# RHN-JD-SCH11V1_00.net
KiCad netlist of a schematic drawn in Altium Designer
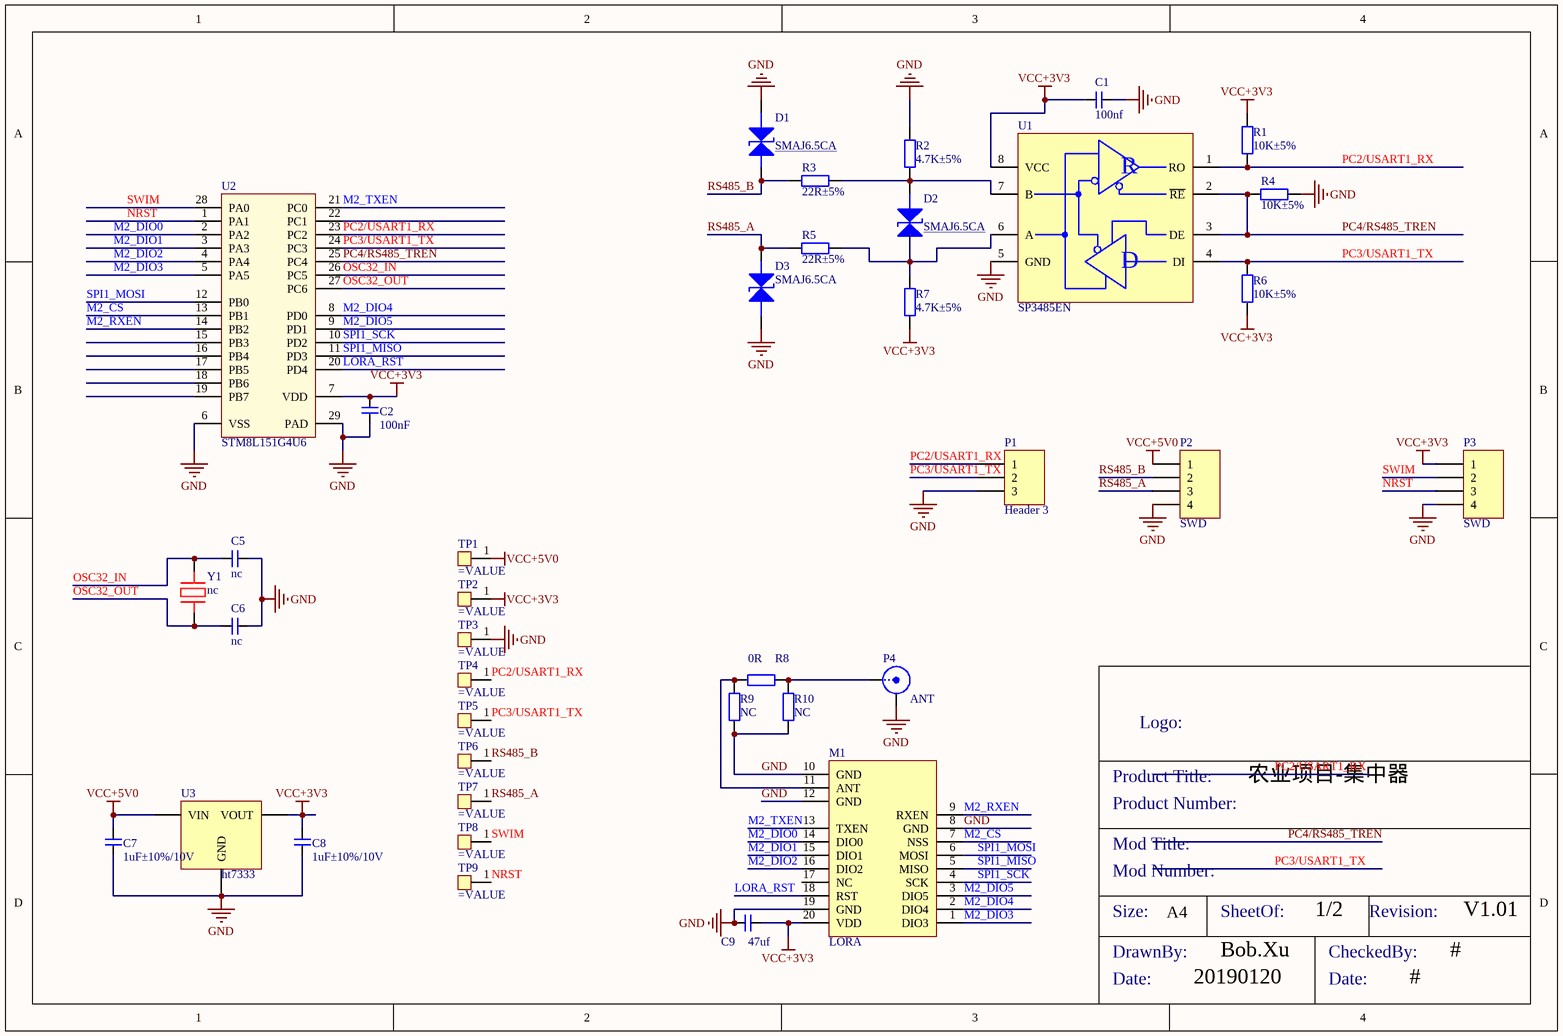
[diagram p0: RHN-JD-SCH11V1.00.SchDoc]

(export (version "E")
  (design (tool "Eeschema 10.0.6"))
  (components
    (comp (ref "C1")
      (value "100nf")
      (footprint "c0402")
      (description "无极性电容")
      (libsource (lib "瑞臻信息") (part "无极性电容"))
    )
    (comp (ref "C2")
      (value "100nF")
      (footprint "C0402")
      (description "无极性电容")
      (libsource (lib "瑞臻信息") (part "无极性电容"))
    )
    (comp (ref "C5")
      (value "nc")
      (footprint "C0402")
      (description "无极性电容")
      (libsource (lib "瑞臻信息") (part "无极性电容"))
    )
    (comp (ref "C6")
      (value "nc")
      (footprint "C0402")
      (description "无极性电容")
      (libsource (lib "瑞臻信息") (part "无极性电容"))
    )
    (comp (ref "C7")
      (value "1uF±10%/10V")
      (footprint "C0402")
      (description "MLCC_1uF±10%_10V_X5R_0402")
      (fields
        (field (name "PART NUMBER") "1.2.04.05.0024")
        (field (name "COMPONENTLINK1URL") "z:\\规格书\\02原材料\\04电容\\05瓷片电容\\三星电容.pdf")
        (field (name "PUBLISHER") "徐永伟")
        (field (name "EDIT NOTE") "V1.0-创建-20190329-徐永伟")
      )
      (libsource (lib "瑞臻信息") (part "无极性电容"))
    )
    (comp (ref "C8")
      (value "1uF±10%/10V")
      (footprint "C0402")
      (description "MLCC_1uF±10%_10V_X5R_0402")
      (fields
        (field (name "PART NUMBER") "1.2.04.05.0024")
        (field (name "COMPONENTLINK1URL") "z:\\规格书\\02原材料\\04电容\\05瓷片电容\\三星电容.pdf")
        (field (name "PUBLISHER") "徐永伟")
        (field (name "EDIT NOTE") "V1.0-创建-20190329-徐永伟")
      )
      (libsource (lib "瑞臻信息") (part "无极性电容"))
    )
    (comp (ref "C9")
      (value "47uf")
      (footprint "瑞臻信息:C1206")
      (description "无极性电容")
      (libsource (lib "瑞臻信息") (part "无极性电容"))
    )
    (comp (ref "D1")
      (value "SMAJ6.5CA")
      (footprint "SMB_2P_3R9X4R6")
      (description "半导体放电管-P821P0080SCLRP-200A(10/160us)-It2.2A/4Vt-6Vdrm-50pF-SMB")
      (libsource (lib "TM03-B_V01") (part "1.2.08.99.0052"))
    )
    (comp (ref "D2")
      (value "SMAJ6.5CA")
      (footprint "SMB_2P_3R9X4R6")
      (description "半导体放电管-P821P0080SCLRP-200A(10/160us)-It2.2A/4Vt-6Vdrm-50pF-SMB")
      (libsource (lib "TM03-B_V01") (part "1.2.08.99.0052"))
    )
    (comp (ref "D3")
      (value "SMAJ6.5CA")
      (footprint "SMB_2P_3R9X4R6")
      (description "半导体放电管-P821P0080SCLRP-200A(10/160us)-It2.2A/4Vt-6Vdrm-50pF-SMB")
      (libsource (lib "TM03-B_V01") (part "1.2.08.99.0052"))
    )
    (comp (ref "M1") (value "LORA") (footprint "LORA_PIN_1") (libsource (lib "瑞臻信息") (part "LORA_PIN_1")))
    (comp (ref "P1")
      (value "Header 3")
      (footprint "HDR1X3")
      (description "Header, 3-Pin")
      (fields (field (name "PUBLISHER") "Altium Limited"))
      (libsource (lib "Miscellaneous Connectors") (part "Header 3"))
    )
    (comp (ref "P2")
      (value "SWD")
      (footprint "HDR1X4")
      (description "Header, 4-Pin")
      (fields (field (name "PUBLISHER") "Altium Limited"))
      (libsource (lib "Miscellaneous Connectors") (part "Header 4"))
    )
    (comp (ref "P3")
      (value "SWD")
      (footprint "HDR1X4")
      (description "Header, 4-Pin")
      (fields (field (name "PUBLISHER") "Altium Limited"))
      (libsource (lib "Miscellaneous Connectors") (part "Header 4"))
    )
    (comp (ref "P4")
      (value "ANT")
      (footprint "BNC_RA CON")
      (description "BNC Elbow Connector")
      (fields (field (name "PUBLISHER") "Altium Limited"))
      (libsource (lib "Miscellaneous Connectors") (part "BNC"))
    )
    (comp (ref "R1")
      (value "10K±5%")
      (footprint "R0402")
      (description "电阻-10K±5%-1/16W-0402")
      (fields
        (field (name "PART NUMBER") "1.2.03.01.0012")
        (field (name "COMPONENTLINK1URL") "z:\\altiumdesigner\\规格书\\02原材料\\03电阻\\01普通电阻\\")
        (field (name "COMPONENTLINK2URL") "z:\\altiumdesigner\\规格书\\02原材料\\03电阻\\01普通电阻\\")
        (field (name "PUBLISHER") "徐永伟")
        (field (name "EDIT NOTE") "V1.0-创建-20161225-徐永伟")
        (field (name "COMPONENTLINK3URL") "z:\\altiumdesigner\\规格书\\02原材料\\03电阻\\01普通电阻\\")
        (field (name "COMPONENTLINK4URL") "z:\\altiumdesigner\\规格书\\02原材料\\03电阻\\01普通电阻\\")
      )
      (libsource (lib "檀木科技") (part "普通电阻"))
    )
    (comp (ref "R2")
      (value "4.7K±5%")
      (footprint "R0402")
      (description "电阻-4.7K±5%-1/16W-0402")
      (fields
        (field (name "PART NUMBER") "1.2.03.01.0366")
        (field (name "COMPONENTLINK1URL") "z:\\altiumdesigner\\规格书\\02原材料\\03电阻\\01普通电阻\\")
        (field (name "COMPONENTLINK2URL") "z:\\altiumdesigner\\规格书\\02原材料\\03电阻\\01普通电阻\\")
        (field (name "PUBLISHER") "徐永伟")
        (field (name "EDIT NOTE") "V1.0-创建-20161225-徐永伟")
        (field (name "COMPONENTLINK3URL") "z:\\altiumdesigner\\规格书\\02原材料\\03电阻\\01普通电阻\\")
        (field (name "COMPONENTLINK4URL") "z:\\altiumdesigner\\规格书\\02原材料\\03电阻\\01普通电阻\\")
      )
      (libsource (lib "檀木科技") (part "普通电阻"))
    )
    (comp (ref "R3")
      (value "22R±5%")
      (footprint "R0402")
      (description "电阻-4.7R±5%-1/16W-0402")
      (fields
        (field (name "PART NUMBER") "1.2.03.01.0573")
        (field (name "COMPONENTLINK1URL") "z:\\altiumdesigner\\规格书\\02原材料\\03电阻\\01普通电阻\\")
        (field (name "COMPONENTLINK2URL") "z:\\altiumdesigner\\规格书\\02原材料\\03电阻\\01普通电阻\\")
        (field (name "PUBLISHER") "徐永伟")
        (field (name "EDIT NOTE") "V1.0-创建-20161225-徐永伟")
        (field (name "COMPONENTLINK3URL") "z:\\altiumdesigner\\规格书\\02原材料\\03电阻\\01普通电阻\\")
        (field (name "COMPONENTLINK4URL") "z:\\altiumdesigner\\规格书\\02原材料\\03电阻\\01普通电阻\\")
      )
      (libsource (lib "") (part "普通电阻_3"))
    )
    (comp (ref "R4")
      (value "10K±5%")
      (footprint "R0402")
      (description "电阻-10K±5%-1/16W-0402")
      (fields
        (field (name "PART NUMBER") "1.2.03.01.0012")
        (field (name "COMPONENTLINK1URL") "z:\\altiumdesigner\\规格书\\02原材料\\03电阻\\01普通电阻\\")
        (field (name "COMPONENTLINK2URL") "z:\\altiumdesigner\\规格书\\02原材料\\03电阻\\01普通电阻\\")
        (field (name "PUBLISHER") "徐永伟")
        (field (name "EDIT NOTE") "V1.0-创建-20161225-徐永伟")
        (field (name "COMPONENTLINK3URL") "z:\\altiumdesigner\\规格书\\02原材料\\03电阻\\01普通电阻\\")
        (field (name "COMPONENTLINK4URL") "z:\\altiumdesigner\\规格书\\02原材料\\03电阻\\01普通电阻\\")
      )
      (libsource (lib "") (part "普通电阻_2"))
    )
    (comp (ref "R5")
      (value "22R±5%")
      (footprint "R0402")
      (description "电阻-4.7R±5%-1/16W-0402")
      (fields
        (field (name "PART NUMBER") "1.2.03.01.0573")
        (field (name "COMPONENTLINK1URL") "z:\\altiumdesigner\\规格书\\02原材料\\03电阻\\01普通电阻\\")
        (field (name "COMPONENTLINK2URL") "z:\\altiumdesigner\\规格书\\02原材料\\03电阻\\01普通电阻\\")
        (field (name "PUBLISHER") "徐永伟")
        (field (name "EDIT NOTE") "V1.0-创建-20161225-徐永伟")
        (field (name "COMPONENTLINK3URL") "z:\\altiumdesigner\\规格书\\02原材料\\03电阻\\01普通电阻\\")
        (field (name "COMPONENTLINK4URL") "z:\\altiumdesigner\\规格书\\02原材料\\03电阻\\01普通电阻\\")
      )
      (libsource (lib "") (part "普通电阻_3"))
    )
    (comp (ref "R6")
      (value "10K±5%")
      (footprint "R0402")
      (description "电阻-10K±5%-1/16W-0402")
      (fields
        (field (name "PART NUMBER") "1.2.03.01.0012")
        (field (name "COMPONENTLINK1URL") "z:\\altiumdesigner\\规格书\\02原材料\\03电阻\\01普通电阻\\")
        (field (name "COMPONENTLINK2URL") "z:\\altiumdesigner\\规格书\\02原材料\\03电阻\\01普通电阻\\")
        (field (name "PUBLISHER") "徐永伟")
        (field (name "EDIT NOTE") "V1.0-创建-20161225-徐永伟")
        (field (name "COMPONENTLINK3URL") "z:\\altiumdesigner\\规格书\\02原材料\\03电阻\\01普通电阻\\")
        (field (name "COMPONENTLINK4URL") "z:\\altiumdesigner\\规格书\\02原材料\\03电阻\\01普通电阻\\")
      )
      (libsource (lib "檀木科技") (part "普通电阻"))
    )
    (comp (ref "R7")
      (value "4.7K±5%")
      (footprint "R0402")
      (description "电阻-4.7K±5%-1/16W-0402")
      (fields
        (field (name "PART NUMBER") "1.2.03.01.0366")
        (field (name "COMPONENTLINK1URL") "z:\\altiumdesigner\\规格书\\02原材料\\03电阻\\01普通电阻\\")
        (field (name "COMPONENTLINK2URL") "z:\\altiumdesigner\\规格书\\02原材料\\03电阻\\01普通电阻\\")
        (field (name "PUBLISHER") "徐永伟")
        (field (name "EDIT NOTE") "V1.0-创建-20161225-徐永伟")
        (field (name "COMPONENTLINK3URL") "z:\\altiumdesigner\\规格书\\02原材料\\03电阻\\01普通电阻\\")
        (field (name "COMPONENTLINK4URL") "z:\\altiumdesigner\\规格书\\02原材料\\03电阻\\01普通电阻\\")
      )
      (libsource (lib "檀木科技") (part "普通电阻"))
    )
    (comp (ref "R8")
      (value "0R")
      (footprint "R0402")
      (description "电阻-10K±5%-1/16W-0402")
      (fields
        (field (name "PART NUMBER") "1.2.03.01.0012")
        (field (name "COMPONENTLINK1URL") "z:\\altiumdesigner\\规格书\\02原材料\\03电阻\\01普通电阻\\")
        (field (name "COMPONENTLINK2URL") "z:\\altiumdesigner\\规格书\\02原材料\\03电阻\\01普通电阻\\")
        (field (name "PUBLISHER") "徐永伟")
        (field (name "EDIT NOTE") "V1.0-创建-20161225-徐永伟")
        (field (name "COMPONENTLINK3URL") "z:\\altiumdesigner\\规格书\\02原材料\\03电阻\\01普通电阻\\")
        (field (name "COMPONENTLINK4URL") "z:\\altiumdesigner\\规格书\\02原材料\\03电阻\\01普通电阻\\")
      )
      (libsource (lib "") (part "普通电阻_1"))
    )
    (comp (ref "R9")
      (value "NC")
      (footprint "R0402")
      (description "电阻-10K±5%-1/16W-0402")
      (fields
        (field (name "PART NUMBER") "1.2.03.01.0012")
        (field (name "COMPONENTLINK1URL") "z:\\altiumdesigner\\规格书\\02原材料\\03电阻\\01普通电阻\\")
        (field (name "COMPONENTLINK2URL") "z:\\altiumdesigner\\规格书\\02原材料\\03电阻\\01普通电阻\\")
        (field (name "PUBLISHER") "徐永伟")
        (field (name "EDIT NOTE") "V1.0-创建-20161225-徐永伟")
        (field (name "COMPONENTLINK3URL") "z:\\altiumdesigner\\规格书\\02原材料\\03电阻\\01普通电阻\\")
        (field (name "COMPONENTLINK4URL") "z:\\altiumdesigner\\规格书\\02原材料\\03电阻\\01普通电阻\\")
      )
      (libsource (lib "") (part "普通电阻_3"))
    )
    (comp (ref "R10")
      (value "NC")
      (footprint "R0402")
      (description "电阻-10K±5%-1/16W-0402")
      (fields
        (field (name "PART NUMBER") "1.2.03.01.0012")
        (field (name "COMPONENTLINK1URL") "z:\\altiumdesigner\\规格书\\02原材料\\03电阻\\01普通电阻\\")
        (field (name "COMPONENTLINK2URL") "z:\\altiumdesigner\\规格书\\02原材料\\03电阻\\01普通电阻\\")
        (field (name "PUBLISHER") "徐永伟")
        (field (name "EDIT NOTE") "V1.0-创建-20161225-徐永伟")
        (field (name "COMPONENTLINK3URL") "z:\\altiumdesigner\\规格书\\02原材料\\03电阻\\01普通电阻\\")
        (field (name "COMPONENTLINK4URL") "z:\\altiumdesigner\\规格书\\02原材料\\03电阻\\01普通电阻\\")
      )
      (libsource (lib "") (part "普通电阻_3"))
    )
    (comp (ref "TP1")
      (value "~")
      (footprint "TP_D1R25")
      (description "测试点")
      (libsource (lib "瑞臻信息") (part "Test_Point"))
    )
    (comp (ref "TP2")
      (value "~")
      (footprint "TP_D1R25")
      (description "测试点")
      (libsource (lib "瑞臻信息") (part "Test_Point"))
    )
    (comp (ref "TP3")
      (value "~")
      (footprint "TP_D1R25")
      (description "测试点")
      (libsource (lib "瑞臻信息") (part "Test_Point"))
    )
    (comp (ref "TP4")
      (value "~")
      (footprint "TP_D1R25")
      (description "测试点")
      (libsource (lib "瑞臻信息") (part "Test_Point"))
    )
    (comp (ref "TP5")
      (value "~")
      (footprint "TP_D1R25")
      (description "测试点")
      (libsource (lib "瑞臻信息") (part "Test_Point"))
    )
    (comp (ref "TP6")
      (value "~")
      (footprint "TP_D1R25")
      (description "测试点")
      (libsource (lib "瑞臻信息") (part "Test_Point"))
    )
    (comp (ref "TP7")
      (value "~")
      (footprint "TP_D1R25")
      (description "测试点")
      (libsource (lib "瑞臻信息") (part "Test_Point"))
    )
    (comp (ref "TP8")
      (value "~")
      (footprint "TP_D1R25")
      (description "测试点")
      (libsource (lib "瑞臻信息") (part "Test_Point"))
    )
    (comp (ref "TP9")
      (value "~")
      (footprint "TP_D1R25")
      (description "测试点")
      (libsource (lib "瑞臻信息") (part "Test_Point"))
    )
    (comp (ref "U1")
      (value "SP3485EN")
      (footprint "SOP_8P_1R27_3R9X4R9")
      (description "RS485收发器-SP3485EN-支持485收发-SOP8")
      (fields
        (field (name "PART NUMBER") "1.2.18.09.0173")
        (field (name "COMPONENTLINK1URL") "Z:\\AltiumDesigner\\规格书\\02原材料\\18集成电路\\09接口芯片\\SP3485EN.pdf")
        (field (name "PUBLISHER") "徐永伟")
        (field (name "EDIT NOTE") "V1.0-创建-20170122-徐永伟")
      )
      (libsource (lib "檀木科技") (part "SP3485"))
    )
    (comp (ref "U2")
      (value "STM8L151G4U6")
      (footprint "QFN_28P_0R5_5R0X5R0_P")
      (libsource (lib "瑞臻信息") (part "STM8L151G4U6"))
    )
    (comp (ref "U3")
      (value "ht7333")
      (footprint "SOT89_3P_1R5_2R5X4R5")
      (description "HT7333_LDO稳压_100mA/3.3V_Vmax=30V_SOT89")
      (fields
        (field (name "PART NUMBER") "1.2.18.07.0002")
        (field (name "COMPONENTLINK1URL") "Z:\\规格书\\02原材料\\18集成电路\\17线性稳压器\\HT7333-3.pdf")
        (field (name "PUBLISHER") "徐永伟")
        (field (name "EDIT NOTE") "V1.0-创建-20180709-徐永伟")
      )
      (libsource (lib "瑞臻信息") (part "HT73XX"))
    )
    (comp (ref "Y1")
      (value "nc")
      (footprint "SMD_Crystal_2P_1R5X3R2")
      (description "两脚晶体谐振器")
      (libsource (lib "瑞臻信息") (part "两脚晶体谐振器"))
    )
  )
  (nets
    (net (code "1") (name "/LORA_RST") (class "Default")
      (node (ref "M1") (pin "18") (pinfunction "RST_18") (pintype "passive"))
      (node (ref "U2") (pin "20") (pinfunction "PD4_20") (pintype "passive"))
    )
    (net (code "2") (name "/M2_CS") (class "Default")
      (node (ref "M1") (pin "7") (pinfunction "NSS_7") (pintype "passive"))
      (node (ref "U2") (pin "13") (pinfunction "PB1_13") (pintype "passive"))
    )
    (net (code "3") (name "/M2_DIO0") (class "Default")
      (node (ref "M1") (pin "14") (pinfunction "DIO0_14") (pintype "passive"))
      (node (ref "U2") (pin "2") (pinfunction "PA2_2") (pintype "passive"))
    )
    (net (code "4") (name "/M2_DIO1") (class "Default")
      (node (ref "M1") (pin "15") (pinfunction "DIO1_15") (pintype "passive"))
      (node (ref "U2") (pin "3") (pinfunction "PA3_3") (pintype "passive"))
    )
    (net (code "5") (name "/M2_DIO2") (class "Default")
      (node (ref "M1") (pin "16") (pinfunction "DIO2_16") (pintype "passive"))
      (node (ref "U2") (pin "4") (pinfunction "PA4_4") (pintype "passive"))
    )
    (net (code "6") (name "/M2_DIO3") (class "Default")
      (node (ref "M1") (pin "1") (pinfunction "DIO3_1") (pintype "passive"))
      (node (ref "U2") (pin "5") (pinfunction "PA5_5") (pintype "passive"))
    )
    (net (code "7") (name "/M2_DIO4") (class "Default")
      (node (ref "M1") (pin "2") (pinfunction "DIO4_2") (pintype "passive"))
      (node (ref "U2") (pin "8") (pinfunction "PD0_8") (pintype "passive"))
    )
    (net (code "8") (name "/M2_DIO5") (class "Default")
      (node (ref "M1") (pin "3") (pinfunction "DIO5_3") (pintype "passive"))
      (node (ref "U2") (pin "9") (pinfunction "PD1_9") (pintype "passive"))
    )
    (net (code "9") (name "/M2_RXEN") (class "Default")
      (node (ref "M1") (pin "9") (pinfunction "RXEN_9") (pintype "passive"))
      (node (ref "U2") (pin "14") (pinfunction "PB2_14") (pintype "passive"))
    )
    (net (code "10") (name "/M2_TXEN") (class "Default")
      (node (ref "M1") (pin "13") (pinfunction "TXEN_13") (pintype "passive"))
      (node (ref "U2") (pin "21") (pinfunction "PC0_21") (pintype "passive"))
    )
    (net (code "11") (name "/NRST") (class "Default")
      (node (ref "P3") (pin "3") (pinfunction "3_3") (pintype "passive"))
      (node (ref "TP9") (pin "1") (pinfunction "1_1") (pintype "passive"))
      (node (ref "U2") (pin "1") (pinfunction "PA1_1") (pintype "passive"))
    )
    (net (code "12") (name "/OSC32_IN") (class "Default")
      (node (ref "C5") (pin "2") (pinfunction "2_2") (pintype "passive"))
      (node (ref "U2") (pin "26") (pinfunction "PC5_26") (pintype "passive"))
      (node (ref "Y1") (pin "2") (pinfunction "2_2") (pintype "passive"))
    )
    (net (code "13") (name "/OSC32_OUT") (class "Default")
      (node (ref "C6") (pin "2") (pinfunction "2_2") (pintype "passive"))
      (node (ref "U2") (pin "27") (pinfunction "PC6_27") (pintype "passive"))
      (node (ref "Y1") (pin "1") (pinfunction "1_1") (pintype "passive"))
    )
    (net (code "14") (name "/PC2{slash}USART1_RX") (class "Default")
      (node (ref "P1") (pin "1") (pinfunction "1_1") (pintype "passive"))
      (node (ref "R1") (pin "1") (pinfunction "1_1") (pintype "passive"))
      (node (ref "TP4") (pin "1") (pinfunction "1_1") (pintype "passive"))
      (node (ref "U1") (pin "1") (pinfunction "RO_1") (pintype "passive"))
      (node (ref "U2") (pin "23") (pinfunction "PC2_23") (pintype "passive"))
    )
    (net (code "15") (name "/PC3{slash}USART1_TX") (class "Default")
      (node (ref "P1") (pin "2") (pinfunction "2_2") (pintype "passive"))
      (node (ref "R6") (pin "2") (pinfunction "2_2") (pintype "passive"))
      (node (ref "TP5") (pin "1") (pinfunction "1_1") (pintype "passive"))
      (node (ref "U1") (pin "4") (pinfunction "DI_4") (pintype "passive"))
      (node (ref "U2") (pin "24") (pinfunction "PC3_24") (pintype "passive"))
    )
    (net (code "16") (name "/PC4{slash}RS485_TREN") (class "Default")
      (node (ref "R4") (pin "1") (pinfunction "1_1") (pintype "passive"))
      (node (ref "U1") (pin "2") (pinfunction "~{RE}_2") (pintype "passive"))
      (node (ref "U1") (pin "3") (pinfunction "DE_3") (pintype "passive"))
      (node (ref "U2") (pin "25") (pinfunction "PC4_25") (pintype "passive"))
    )
    (net (code "17") (name "/RS485_A") (class "Default")
      (node (ref "D3") (pin "1") (pinfunction "A_1") (pintype "passive"))
      (node (ref "P2") (pin "3") (pinfunction "3_3") (pintype "passive"))
      (node (ref "R5") (pin "2") (pinfunction "2_2") (pintype "passive"))
      (node (ref "TP7") (pin "1") (pinfunction "1_1") (pintype "passive"))
    )
    (net (code "18") (name "/RS485_B") (class "Default")
      (node (ref "D1") (pin "1") (pinfunction "A_1") (pintype "passive"))
      (node (ref "P2") (pin "2") (pinfunction "2_2") (pintype "passive"))
      (node (ref "R3") (pin "2") (pinfunction "2_2") (pintype "passive"))
      (node (ref "TP6") (pin "1") (pinfunction "1_1") (pintype "passive"))
    )
    (net (code "19") (name "/SPI1_MISO") (class "Default")
      (node (ref "M1") (pin "5") (pinfunction "MISO_5") (pintype "passive"))
      (node (ref "U2") (pin "11") (pinfunction "PD3_11") (pintype "passive"))
    )
    (net (code "20") (name "/SPI1_MOSI") (class "Default")
      (node (ref "M1") (pin "6") (pinfunction "MOSI_6") (pintype "passive"))
      (node (ref "U2") (pin "12") (pinfunction "PB0_12") (pintype "passive"))
    )
    (net (code "21") (name "/SPI1_SCK") (class "Default")
      (node (ref "M1") (pin "4") (pinfunction "SCK_4") (pintype "passive"))
      (node (ref "U2") (pin "10") (pinfunction "PD2_10") (pintype "passive"))
    )
    (net (code "22") (name "/SWIM") (class "Default")
      (node (ref "P3") (pin "2") (pinfunction "2_2") (pintype "passive"))
      (node (ref "TP8") (pin "1") (pinfunction "1_1") (pintype "passive"))
      (node (ref "U2") (pin "28") (pinfunction "PA0_28") (pintype "passive"))
    )
    (net (code "23") (name "GND") (class "Default")
      (node (ref "C1") (pin "2") (pinfunction "2_2") (pintype "passive"))
      (node (ref "C2") (pin "1") (pinfunction "1_1") (pintype "passive"))
      (node (ref "C5") (pin "1") (pinfunction "1_1") (pintype "passive"))
      (node (ref "C6") (pin "1") (pinfunction "1_1") (pintype "passive"))
      (node (ref "C7") (pin "1") (pinfunction "1_1") (pintype "passive"))
      (node (ref "C8") (pin "1") (pinfunction "1_1") (pintype "passive"))
      (node (ref "C9") (pin "1") (pinfunction "1_1") (pintype "passive"))
      (node (ref "D1") (pin "2") (pinfunction "K_2") (pintype "passive"))
      (node (ref "D3") (pin "2") (pinfunction "K_2") (pintype "passive"))
      (node (ref "M1") (pin "10") (pinfunction "GND_10") (pintype "passive"))
      (node (ref "M1") (pin "12") (pinfunction "GND_12") (pintype "passive"))
      (node (ref "M1") (pin "19") (pinfunction "GND_19") (pintype "passive"))
      (node (ref "M1") (pin "8") (pinfunction "GND_8") (pintype "passive"))
      (node (ref "P1") (pin "3") (pinfunction "3_3") (pintype "passive"))
      (node (ref "P2") (pin "4") (pinfunction "4_4") (pintype "passive"))
      (node (ref "P3") (pin "4") (pinfunction "4_4") (pintype "passive"))
      (node (ref "P4") (pin "2") (pinfunction "Y_2") (pintype "passive"))
      (node (ref "R10") (pin "2") (pinfunction "2_2") (pintype "passive"))
      (node (ref "R2") (pin "2") (pinfunction "2_2") (pintype "passive"))
      (node (ref "R4") (pin "2") (pinfunction "2_2") (pintype "passive"))
      (node (ref "R9") (pin "2") (pinfunction "2_2") (pintype "passive"))
      (node (ref "TP3") (pin "1") (pinfunction "1_1") (pintype "passive"))
      (node (ref "U1") (pin "5") (pinfunction "GND_5") (pintype "passive"))
      (node (ref "U2") (pin "29") (pinfunction "PAD_29") (pintype "passive"))
      (node (ref "U2") (pin "6") (pinfunction "VSS_6") (pintype "passive"))
      (node (ref "U3") (pin "1") (pinfunction "GND_1") (pintype "passive"))
    )
    (net (code "24") (name "Net-(D2-A)") (class "Default")
      (node (ref "D2") (pin "1") (pinfunction "A_1") (pintype "passive"))
      (node (ref "R5") (pin "1") (pinfunction "1_1") (pintype "passive"))
      (node (ref "R7") (pin "2") (pinfunction "2_2") (pintype "passive"))
      (node (ref "U1") (pin "6") (pinfunction "A_6") (pintype "passive"))
    )
    (net (code "25") (name "Net-(D2-K)") (class "Default")
      (node (ref "D2") (pin "2") (pinfunction "K_2") (pintype "passive"))
      (node (ref "R2") (pin "1") (pinfunction "1_1") (pintype "passive"))
      (node (ref "R3") (pin "1") (pinfunction "1_1") (pintype "passive"))
      (node (ref "U1") (pin "7") (pinfunction "B_7") (pintype "passive"))
    )
    (net (code "26") (name "Net-(M1-ANT)") (class "Default")
      (node (ref "M1") (pin "11") (pinfunction "ANT_11") (pintype "passive"))
      (node (ref "R8") (pin "2") (pinfunction "2_2") (pintype "passive"))
      (node (ref "R9") (pin "1") (pinfunction "1_1") (pintype "passive"))
    )
    (net (code "27") (name "Net-(P4-X)") (class "Default")
      (node (ref "P4") (pin "1") (pinfunction "X_1") (pintype "passive"))
      (node (ref "R10") (pin "1") (pinfunction "1_1") (pintype "passive"))
      (node (ref "R8") (pin "1") (pinfunction "1_1") (pintype "passive"))
    )
    (net (code "28") (name "VCC+3V3") (class "Default")
      (node (ref "C1") (pin "1") (pinfunction "1_1") (pintype "passive"))
      (node (ref "C2") (pin "2") (pinfunction "2_2") (pintype "passive"))
      (node (ref "C8") (pin "2") (pinfunction "2_2") (pintype "passive"))
      (node (ref "C9") (pin "2") (pinfunction "2_2") (pintype "passive"))
      (node (ref "M1") (pin "20") (pinfunction "VDD_20") (pintype "passive"))
      (node (ref "P3") (pin "1") (pinfunction "1_1") (pintype "passive"))
      (node (ref "R1") (pin "2") (pinfunction "2_2") (pintype "passive"))
      (node (ref "R6") (pin "1") (pinfunction "1_1") (pintype "passive"))
      (node (ref "R7") (pin "1") (pinfunction "1_1") (pintype "passive"))
      (node (ref "TP2") (pin "1") (pinfunction "1_1") (pintype "passive"))
      (node (ref "U1") (pin "8") (pinfunction "VCC_8") (pintype "passive"))
      (node (ref "U2") (pin "7") (pinfunction "VDD_7") (pintype "passive"))
      (node (ref "U3") (pin "3") (pinfunction "VOUT_3") (pintype "passive"))
    )
    (net (code "29") (name "VCC+5V0") (class "Default")
      (node (ref "C7") (pin "2") (pinfunction "2_2") (pintype "passive"))
      (node (ref "P2") (pin "1") (pinfunction "1_1") (pintype "passive"))
      (node (ref "TP1") (pin "1") (pinfunction "1_1") (pintype "passive"))
      (node (ref "U3") (pin "2") (pinfunction "VIN_2") (pintype "passive"))
    )
    (net (code "30") (name "unconnected-(M1-NC-Pad17)") (class "Default")
      (node (ref "M1") (pin "17") (pinfunction "NC_17") (pintype "passive"))
    )
    (net (code "31") (name "unconnected-(U2-PB3-Pad15)") (class "Default")
      (node (ref "U2") (pin "15") (pinfunction "PB3_15") (pintype "passive"))
    )
    (net (code "32") (name "unconnected-(U2-PB4-Pad16)") (class "Default")
      (node (ref "U2") (pin "16") (pinfunction "PB4_16") (pintype "passive"))
    )
    (net (code "33") (name "unconnected-(U2-PB5-Pad17)") (class "Default")
      (node (ref "U2") (pin "17") (pinfunction "PB5_17") (pintype "passive"))
    )
    (net (code "34") (name "unconnected-(U2-PB6-Pad18)") (class "Default")
      (node (ref "U2") (pin "18") (pinfunction "PB6_18") (pintype "passive"))
    )
    (net (code "35") (name "unconnected-(U2-PB7-Pad19)") (class "Default")
      (node (ref "U2") (pin "19") (pinfunction "PB7_19") (pintype "passive"))
    )
    (net (code "36") (name "unconnected-(U2-PC1-Pad22)") (class "Default")
      (node (ref "U2") (pin "22") (pinfunction "PC1_22") (pintype "passive"))
    )
  )
)
